# anpu.net
KiCad netlist of a schematic drawn in EAGLE
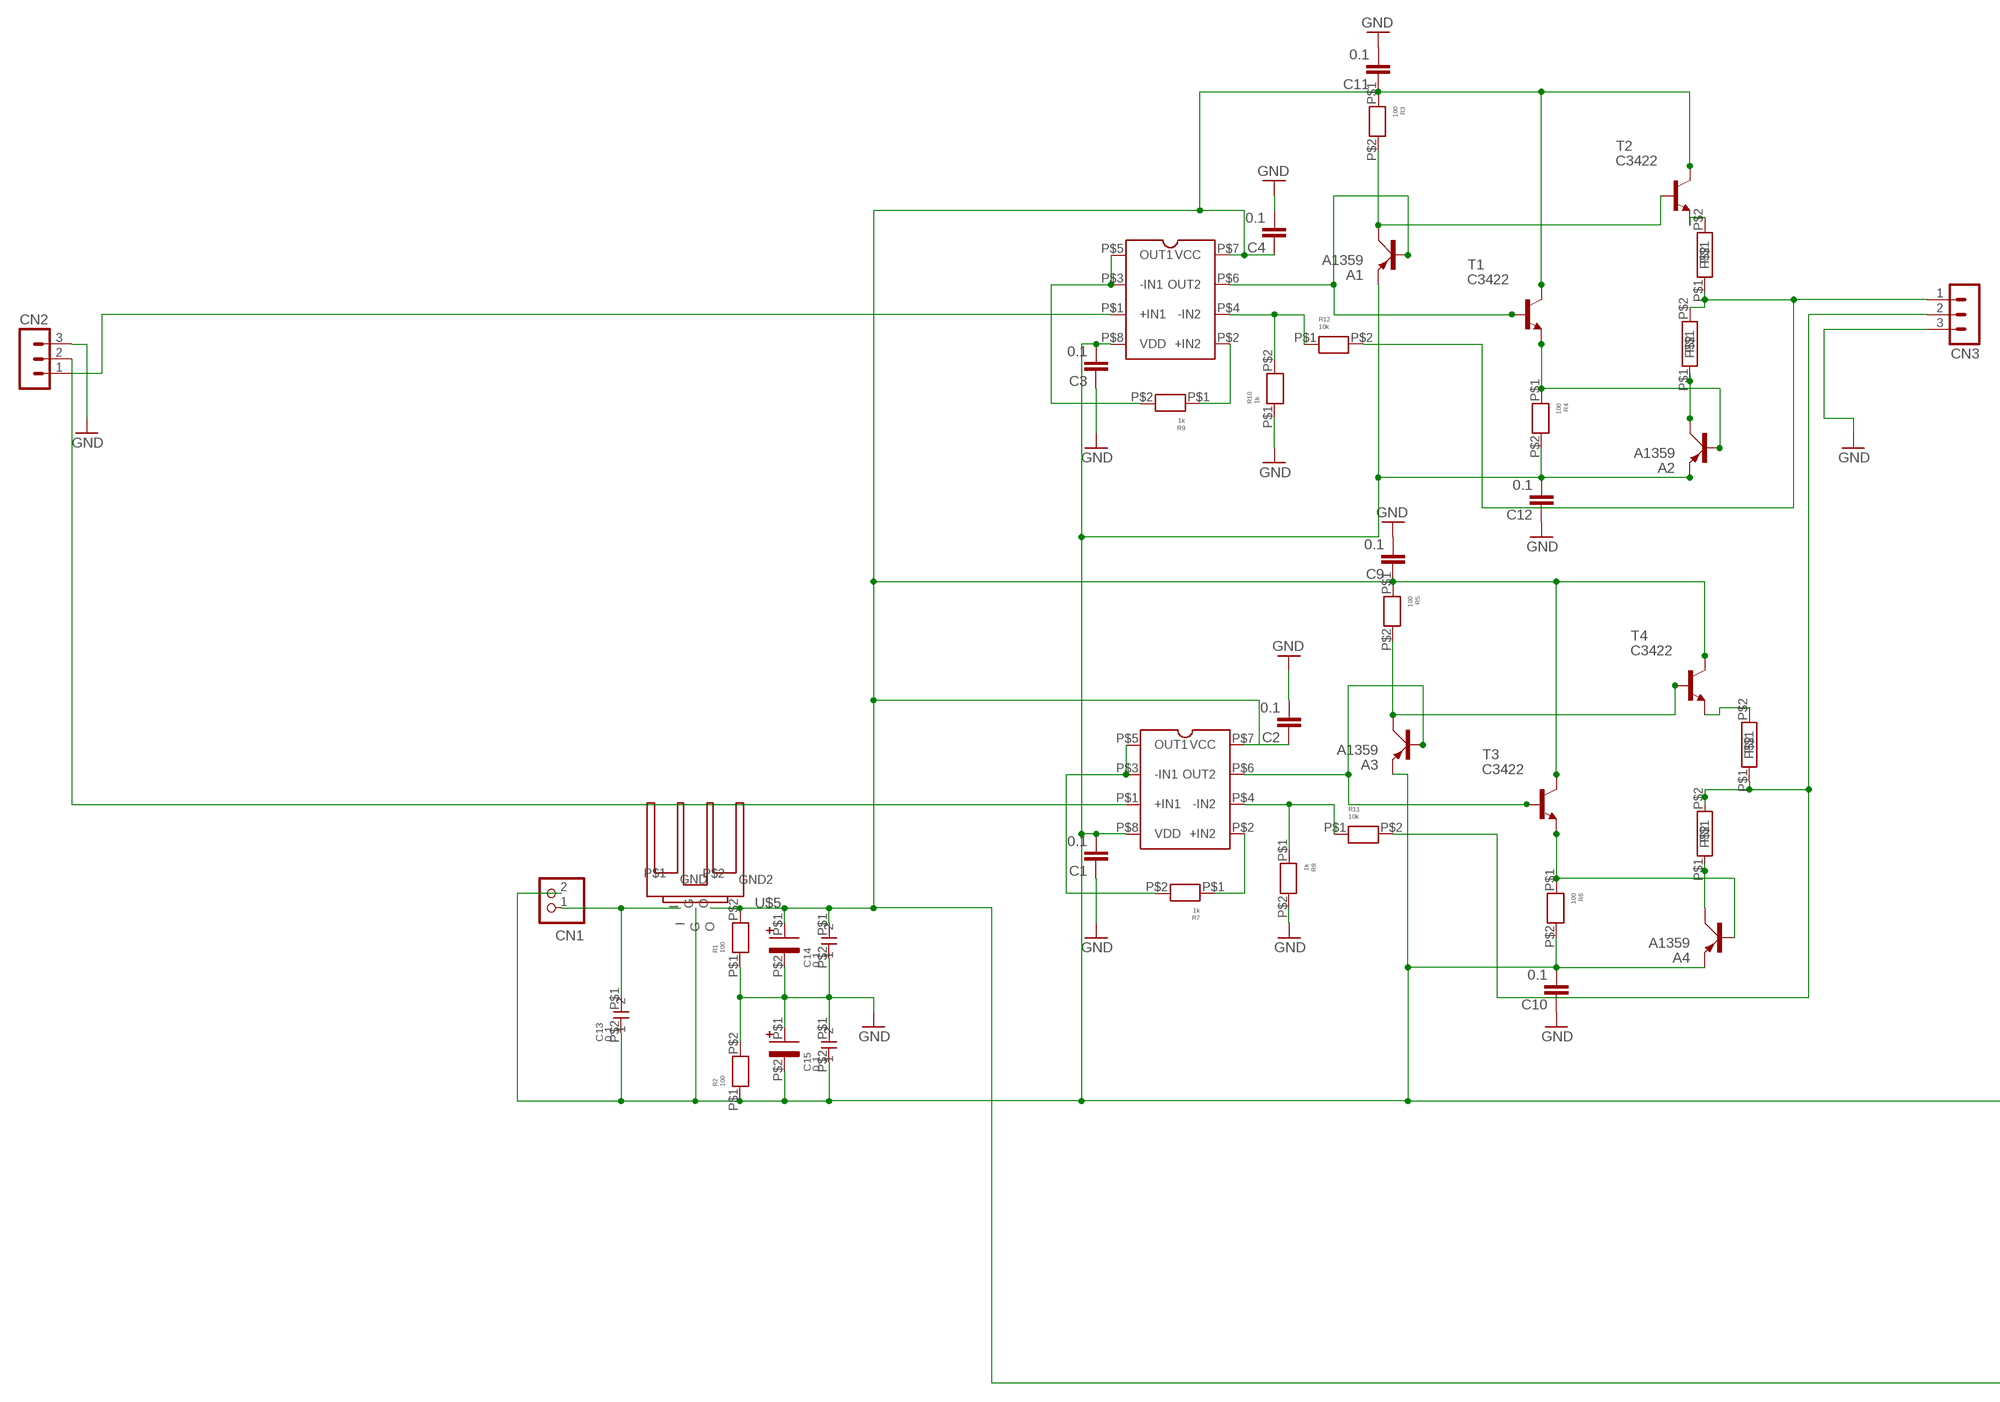
[diagram p0: schematic, sheet 1, part 1 of 2]
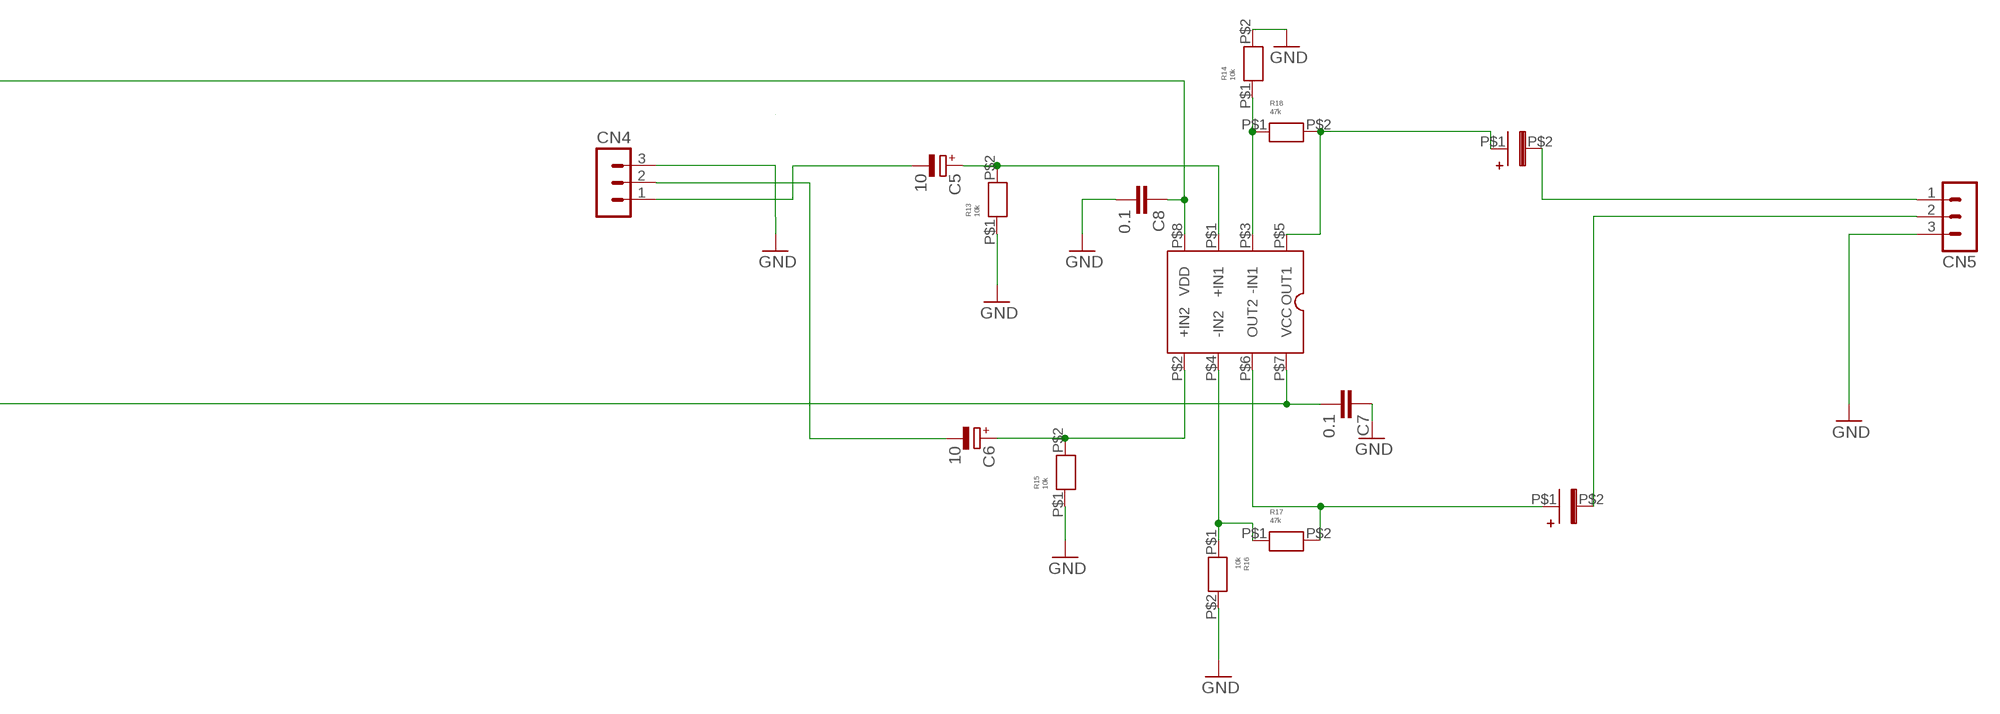
[diagram p1: schematic, sheet 1, part 2 of 2]

(export (version "E")
  (design (tool "Eeschema 10.0.6"))
  (components
    (comp (ref "A1")
      (value "A1359")
      (footprint "eagle-import:TO220AV")
      (libsource (lib "eagle-import") (part "MJE2955"))
    )
    (comp (ref "A2")
      (value "A1359")
      (footprint "eagle-import:TO220AV")
      (libsource (lib "eagle-import") (part "MJE2955"))
    )
    (comp (ref "A3")
      (value "A1359")
      (footprint "eagle-import:TO220AV")
      (libsource (lib "eagle-import") (part "MJE2955"))
    )
    (comp (ref "A4")
      (value "A1359")
      (footprint "eagle-import:TO220AV")
      (libsource (lib "eagle-import") (part "MJE2955"))
    )
    (comp (ref "C1")
      (value "0.1")
      (footprint "eagle-import:C050-030X075")
      (libsource (lib "eagle-import") (part "C-EU050-030X075"))
    )
    (comp (ref "C2")
      (value "0.1")
      (footprint "eagle-import:C050-030X075")
      (libsource (lib "eagle-import") (part "C-EU050-030X075"))
    )
    (comp (ref "C3")
      (value "0.1")
      (footprint "eagle-import:C050-030X075")
      (libsource (lib "eagle-import") (part "C-EU050-030X075"))
    )
    (comp (ref "C4")
      (value "0.1")
      (footprint "eagle-import:C050-030X075")
      (libsource (lib "eagle-import") (part "C-EU050-030X075"))
    )
    (comp (ref "C5")
      (value "10")
      (footprint "eagle-import:E2,5-5")
      (libsource (lib "eagle-import") (part "CPOL-EUE2.5-5"))
    )
    (comp (ref "C6")
      (value "10")
      (footprint "eagle-import:E2,5-5")
      (libsource (lib "eagle-import") (part "CPOL-EUE2.5-5"))
    )
    (comp (ref "C7")
      (value "0.1")
      (footprint "eagle-import:C050-030X075")
      (libsource (lib "eagle-import") (part "C-EU050-030X075"))
    )
    (comp (ref "C8")
      (value "0.1")
      (footprint "eagle-import:C050-030X075")
      (libsource (lib "eagle-import") (part "C-EU050-030X075"))
    )
    (comp (ref "C9")
      (value "0.1")
      (footprint "eagle-import:C050-030X075")
      (libsource (lib "eagle-import") (part "C-EU050-030X075"))
    )
    (comp (ref "C10")
      (value "0.1")
      (footprint "eagle-import:C050-030X075")
      (libsource (lib "eagle-import") (part "C-EU050-030X075"))
    )
    (comp (ref "C11")
      (value "0.1")
      (footprint "eagle-import:C050-030X075")
      (libsource (lib "eagle-import") (part "C-EU050-030X075"))
    )
    (comp (ref "C12")
      (value "0.1")
      (footprint "eagle-import:C050-030X075")
      (libsource (lib "eagle-import") (part "C-EU050-030X075"))
    )
    (comp (ref "C13")
      (value "0.1")
      (footprint "eagle-import:CON")
      (libsource (lib "eagle-import") (part "1608"))
    )
    (comp (ref "C14")
      (value "0.1")
      (footprint "eagle-import:CON")
      (libsource (lib "eagle-import") (part "1608"))
    )
    (comp (ref "C15")
      (value "0.1")
      (footprint "eagle-import:CON")
      (libsource (lib "eagle-import") (part "1608"))
    )
    (comp (ref "CN1")
      (value "B2B-XH-A")
      (footprint "eagle-import:B2B-XH-A")
      (libsource (lib "eagle-import") (part "B2B-XH-A"))
    )
    (comp (ref "CN2")
      (value "B3B-PH-K-S")
      (footprint "eagle-import:B3B-PH-K-S")
      (libsource (lib "eagle-import") (part "B3B-PH-K-S"))
    )
    (comp (ref "CN3")
      (value "B3B-PH-K-S")
      (footprint "eagle-import:B3B-PH-K-S")
      (libsource (lib "eagle-import") (part "B3B-PH-K-S"))
    )
    (comp (ref "CN4")
      (value "B3B-PH-K-S")
      (footprint "eagle-import:B3B-PH-K-S")
      (libsource (lib "eagle-import") (part "B3B-PH-K-S"))
    )
    (comp (ref "CN5")
      (value "B3B-PH-K-S")
      (footprint "eagle-import:B3B-PH-K-S")
      (libsource (lib "eagle-import") (part "B3B-PH-K-S"))
    )
    (comp (ref "EC1") (value "FG") (footprint "eagle-import:FG") (libsource (lib "eagle-import") (part "FG")))
    (comp (ref "EC2") (value "FG") (footprint "eagle-import:FG") (libsource (lib "eagle-import") (part "FG")))
    (comp (ref "EC3") (value "FG") (footprint "eagle-import:FG") (libsource (lib "eagle-import") (part "FG")))
    (comp (ref "EC4") (value "FG") (footprint "eagle-import:FG") (libsource (lib "eagle-import") (part "FG")))
    (comp (ref "R1")
      (value "100")
      (footprint "eagle-import:1608")
      (libsource (lib "eagle-import") (part "R"))
    )
    (comp (ref "R2")
      (value "100")
      (footprint "eagle-import:1608")
      (libsource (lib "eagle-import") (part "R"))
    )
    (comp (ref "R3")
      (value "100")
      (footprint "eagle-import:1608")
      (libsource (lib "eagle-import") (part "R"))
    )
    (comp (ref "R4")
      (value "100")
      (footprint "eagle-import:1608")
      (libsource (lib "eagle-import") (part "R"))
    )
    (comp (ref "R5")
      (value "100")
      (footprint "eagle-import:1608")
      (libsource (lib "eagle-import") (part "R"))
    )
    (comp (ref "R6")
      (value "100")
      (footprint "eagle-import:1608")
      (libsource (lib "eagle-import") (part "R"))
    )
    (comp (ref "R7") (value "1k") (footprint "eagle-import:1608") (libsource (lib "eagle-import") (part "R")))
    (comp (ref "R8") (value "1k") (footprint "eagle-import:1608") (libsource (lib "eagle-import") (part "R")))
    (comp (ref "R9") (value "1k") (footprint "eagle-import:1608") (libsource (lib "eagle-import") (part "R")))
    (comp (ref "R10")
      (value "1k")
      (footprint "eagle-import:1608")
      (libsource (lib "eagle-import") (part "R"))
    )
    (comp (ref "R11")
      (value "10k")
      (footprint "eagle-import:1608")
      (libsource (lib "eagle-import") (part "R"))
    )
    (comp (ref "R12")
      (value "10k")
      (footprint "eagle-import:1608")
      (libsource (lib "eagle-import") (part "R"))
    )
    (comp (ref "R13")
      (value "10k")
      (footprint "eagle-import:1608")
      (libsource (lib "eagle-import") (part "R"))
    )
    (comp (ref "R14")
      (value "10k")
      (footprint "eagle-import:1608")
      (libsource (lib "eagle-import") (part "R"))
    )
    (comp (ref "R15")
      (value "10k")
      (footprint "eagle-import:1608")
      (libsource (lib "eagle-import") (part "R"))
    )
    (comp (ref "R16")
      (value "10k")
      (footprint "eagle-import:1608")
      (libsource (lib "eagle-import") (part "R"))
    )
    (comp (ref "R17")
      (value "47k")
      (footprint "eagle-import:1608")
      (libsource (lib "eagle-import") (part "R"))
    )
    (comp (ref "R18")
      (value "47k")
      (footprint "eagle-import:1608")
      (libsource (lib "eagle-import") (part "R"))
    )
    (comp (ref "T1")
      (value "C3422")
      (footprint "eagle-import:TO220AV")
      (libsource (lib "eagle-import") (part "2SC3212V"))
    )
    (comp (ref "T2")
      (value "C3422")
      (footprint "eagle-import:TO220AV")
      (libsource (lib "eagle-import") (part "2SC3212V"))
    )
    (comp (ref "T3")
      (value "C3422")
      (footprint "eagle-import:TO220AV")
      (libsource (lib "eagle-import") (part "2SC3212V"))
    )
    (comp (ref "T4")
      (value "C3422")
      (footprint "eagle-import:TO220AV")
      (libsource (lib "eagle-import") (part "2SC3212V"))
    )
    (comp (ref "U$1")
      (value "4580DD")
      (footprint "eagle-import:4580DD")
      (libsource (lib "eagle-import") (part "4580DD"))
    )
    (comp (ref "U$4")
      (value "4580DD")
      (footprint "eagle-import:4580DD")
      (libsource (lib "eagle-import") (part "4580DD"))
    )
    (comp (ref "U$5")
      (value "CONVERTER")
      (footprint "eagle-import:CONVERTER")
      (libsource (lib "eagle-import") (part "CONVERTER"))
    )
    (comp (ref "U$6")
      (value "4580DD")
      (footprint "eagle-import:4580DD")
      (libsource (lib "eagle-import") (part "4580DD"))
    )
    (comp (ref "U$36")
      (value "0.47")
      (footprint "eagle-import:KINZOKUTEIKOU")
      (libsource (lib "eagle-import") (part "KINZOKUTEIKOU"))
    )
    (comp (ref "U$37")
      (value "0.47")
      (footprint "eagle-import:KINZOKUTEIKOU")
      (libsource (lib "eagle-import") (part "KINZOKUTEIKOU"))
    )
    (comp (ref "U$38")
      (value "0.47")
      (footprint "eagle-import:KINZOKUTEIKOU")
      (libsource (lib "eagle-import") (part "KINZOKUTEIKOU"))
    )
    (comp (ref "U$39")
      (value "0.47")
      (footprint "eagle-import:KINZOKUTEIKOU")
      (libsource (lib "eagle-import") (part "KINZOKUTEIKOU"))
    )
  )
  (nets
    (net (code "1") (name "GND") (class "Default")
      (node (ref "C1") (pin "1") (pinfunction "1_1") (pintype "passive"))
      (node (ref "C10") (pin "1") (pinfunction "1_1") (pintype "passive"))
      (node (ref "C11") (pin "2") (pinfunction "2_2") (pintype "passive"))
      (node (ref "C12") (pin "1") (pinfunction "1_1") (pintype "passive"))
      (node (ref "C14") (pin "P$2") (pinfunction "2_P$2") (pintype "bidirectional"))
      (node (ref "C15") (pin "P$1") (pinfunction "1_P$1") (pintype "bidirectional"))
      (node (ref "C2") (pin "2") (pinfunction "2_2") (pintype "passive"))
      (node (ref "C3") (pin "1") (pinfunction "1_1") (pintype "passive"))
      (node (ref "C4") (pin "2") (pinfunction "2_2") (pintype "passive"))
      (node (ref "C7") (pin "1") (pinfunction "1_1") (pintype "passive"))
      (node (ref "C8") (pin "2") (pinfunction "2_2") (pintype "passive"))
      (node (ref "C9") (pin "2") (pinfunction "2_2") (pintype "passive"))
      (node (ref "CN2") (pin "3") (pinfunction "3_3") (pintype "passive"))
      (node (ref "CN3") (pin "3") (pinfunction "3_3") (pintype "passive"))
      (node (ref "CN5") (pin "3") (pinfunction "3_3") (pintype "passive"))
      (node (ref "EC3") (pin "P$2") (pinfunction "P$1_P$2") (pintype "bidirectional"))
      (node (ref "EC4") (pin "P$1") (pinfunction "P$2_P$1") (pintype "bidirectional"))
      (node (ref "R1") (pin "P$1") (pinfunction "P$1_P$1") (pintype "bidirectional"))
      (node (ref "R10") (pin "P$1") (pinfunction "P$1_P$1") (pintype "bidirectional"))
      (node (ref "R13") (pin "P$1") (pinfunction "P$1_P$1") (pintype "bidirectional"))
      (node (ref "R14") (pin "P$2") (pinfunction "P$2_P$2") (pintype "bidirectional"))
      (node (ref "R15") (pin "P$1") (pinfunction "P$1_P$1") (pintype "bidirectional"))
      (node (ref "R16") (pin "P$2") (pinfunction "P$2_P$2") (pintype "bidirectional"))
      (node (ref "R2") (pin "P$2") (pinfunction "P$2_P$2") (pintype "bidirectional"))
      (node (ref "R8") (pin "P$2") (pinfunction "P$2_P$2") (pintype "bidirectional"))
    )
    (net (code "2") (name "Net-(A2-PadC)") (class "Default")
      (node (ref "A2") (pin "C") (pinfunction "C_C") (pintype "passive"))
      (node (ref "U$36") (pin "P$1") (pinfunction "P$1_P$1") (pintype "bidirectional"))
    )
    (net (code "3") (name "Net-(A4-PadC)") (class "Default")
      (node (ref "A4") (pin "C") (pinfunction "C_C") (pintype "passive"))
      (node (ref "U$39") (pin "P$1") (pinfunction "P$1_P$1") (pintype "bidirectional"))
    )
    (net (code "4") (name "Net-(C5-Pad-)") (class "Default")
      (node (ref "C5") (pin "-") (pinfunction "-_-") (pintype "passive"))
      (node (ref "CN4") (pin "1") (pinfunction "1_1") (pintype "passive"))
    )
    (net (code "5") (name "Net-(C6-Pad-)") (class "Default")
      (node (ref "C6") (pin "-") (pinfunction "-_-") (pintype "passive"))
      (node (ref "CN4") (pin "2") (pinfunction "2_2") (pintype "passive"))
    )
    (net (code "6") (name "Net-(C13-1)") (class "Default")
      (node (ref "C13") (pin "P$1") (pinfunction "1_P$1") (pintype "bidirectional"))
      (node (ref "CN1") (pin "1") (pinfunction "1_1") (pintype "passive"))
      (node (ref "U$5") (pin "I") (pinfunction "I_I") (pintype "bidirectional"))
    )
    (net (code "7") (name "Net-(C13-2)") (class "Default")
      (node (ref "A1") (pin "E") (pinfunction "E_E") (pintype "passive"))
      (node (ref "A2") (pin "E") (pinfunction "E_E") (pintype "passive"))
      (node (ref "A3") (pin "E") (pinfunction "E_E") (pintype "passive"))
      (node (ref "A4") (pin "E") (pinfunction "E_E") (pintype "passive"))
      (node (ref "C1") (pin "2") (pinfunction "2_2") (pintype "passive"))
      (node (ref "C10") (pin "2") (pinfunction "2_2") (pintype "passive"))
      (node (ref "C12") (pin "2") (pinfunction "2_2") (pintype "passive"))
      (node (ref "C13") (pin "P$2") (pinfunction "2_P$2") (pintype "bidirectional"))
      (node (ref "C15") (pin "P$2") (pinfunction "2_P$2") (pintype "bidirectional"))
      (node (ref "C3") (pin "2") (pinfunction "2_2") (pintype "passive"))
      (node (ref "C8") (pin "1") (pinfunction "1_1") (pintype "passive"))
      (node (ref "CN1") (pin "2") (pinfunction "2_2") (pintype "passive"))
      (node (ref "EC4") (pin "P$2") (pinfunction "P$1_P$2") (pintype "bidirectional"))
      (node (ref "R2") (pin "P$1") (pinfunction "P$1_P$1") (pintype "bidirectional"))
      (node (ref "R4") (pin "P$2") (pinfunction "P$2_P$2") (pintype "bidirectional"))
      (node (ref "R6") (pin "P$2") (pinfunction "P$2_P$2") (pintype "bidirectional"))
      (node (ref "U$1") (pin "P$8") (pinfunction "VDD_P$8") (pintype "bidirectional"))
      (node (ref "U$4") (pin "P$8") (pinfunction "VDD_P$8") (pintype "bidirectional"))
      (node (ref "U$5") (pin "G") (pinfunction "G_G") (pintype "bidirectional"))
      (node (ref "U$6") (pin "P$8") (pinfunction "VDD_P$8") (pintype "bidirectional"))
    )
    (net (code "8") (name "Net-(C14-1)") (class "Default")
      (node (ref "C11") (pin "1") (pinfunction "1_1") (pintype "passive"))
      (node (ref "C14") (pin "P$1") (pinfunction "1_P$1") (pintype "bidirectional"))
      (node (ref "C2") (pin "1") (pinfunction "1_1") (pintype "passive"))
      (node (ref "C4") (pin "1") (pinfunction "1_1") (pintype "passive"))
      (node (ref "C7") (pin "2") (pinfunction "2_2") (pintype "passive"))
      (node (ref "C9") (pin "1") (pinfunction "1_1") (pintype "passive"))
      (node (ref "EC3") (pin "P$1") (pinfunction "P$2_P$1") (pintype "bidirectional"))
      (node (ref "R1") (pin "P$2") (pinfunction "P$2_P$2") (pintype "bidirectional"))
      (node (ref "R3") (pin "P$1") (pinfunction "P$1_P$1") (pintype "bidirectional"))
      (node (ref "R5") (pin "P$1") (pinfunction "P$1_P$1") (pintype "bidirectional"))
      (node (ref "T1") (pin "2") (pinfunction "C_2") (pintype "passive"))
      (node (ref "T2") (pin "2") (pinfunction "C_2") (pintype "passive"))
      (node (ref "T3") (pin "2") (pinfunction "C_2") (pintype "passive"))
      (node (ref "T4") (pin "2") (pinfunction "C_2") (pintype "passive"))
      (node (ref "U$1") (pin "P$7") (pinfunction "VCC_P$7") (pintype "bidirectional"))
      (node (ref "U$4") (pin "P$7") (pinfunction "VCC_P$7") (pintype "bidirectional"))
      (node (ref "U$5") (pin "O") (pinfunction "O_O") (pintype "bidirectional"))
      (node (ref "U$6") (pin "P$7") (pinfunction "VCC_P$7") (pintype "bidirectional"))
    )
    (net (code "9") (name "Net-(CN3-Pad1)") (class "Default")
      (node (ref "CN3") (pin "1") (pinfunction "1_1") (pintype "passive"))
      (node (ref "R12") (pin "P$2") (pinfunction "P$2_P$2") (pintype "bidirectional"))
      (node (ref "U$36") (pin "P$2") (pinfunction "P$2_P$2") (pintype "bidirectional"))
      (node (ref "U$37") (pin "P$1") (pinfunction "P$1_P$1") (pintype "bidirectional"))
    )
    (net (code "10") (name "Net-(CN3-Pad2)") (class "Default")
      (node (ref "CN3") (pin "2") (pinfunction "2_2") (pintype "passive"))
      (node (ref "R11") (pin "P$2") (pinfunction "P$2_P$2") (pintype "bidirectional"))
      (node (ref "U$38") (pin "P$1") (pinfunction "P$1_P$1") (pintype "bidirectional"))
      (node (ref "U$39") (pin "P$2") (pinfunction "P$2_P$2") (pintype "bidirectional"))
    )
    (net (code "11") (name "Net-(EC1-P$1)") (class "Default")
      (node (ref "CN5") (pin "2") (pinfunction "2_2") (pintype "passive"))
      (node (ref "EC1") (pin "P$2") (pinfunction "P$1_P$2") (pintype "bidirectional"))
    )
    (net (code "12") (name "Net-(EC1-P$2)") (class "Default")
      (node (ref "EC1") (pin "P$1") (pinfunction "P$2_P$1") (pintype "bidirectional"))
      (node (ref "R17") (pin "P$2") (pinfunction "P$2_P$2") (pintype "bidirectional"))
      (node (ref "U$6") (pin "P$6") (pinfunction "OUT2_P$6") (pintype "bidirectional"))
    )
    (net (code "13") (name "Net-(EC2-P$1)") (class "Default")
      (node (ref "CN5") (pin "1") (pinfunction "1_1") (pintype "passive"))
      (node (ref "EC2") (pin "P$2") (pinfunction "P$1_P$2") (pintype "bidirectional"))
    )
    (net (code "14") (name "Net-(EC2-P$2)") (class "Default")
      (node (ref "EC2") (pin "P$1") (pinfunction "P$2_P$1") (pintype "bidirectional"))
      (node (ref "R18") (pin "P$2") (pinfunction "P$2_P$2") (pintype "bidirectional"))
      (node (ref "U$6") (pin "P$5") (pinfunction "OUT1_P$5") (pintype "bidirectional"))
    )
    (net (code "15") (name "Net-(T1-B)") (class "Default")
      (node (ref "A1") (pin "B") (pinfunction "B_B") (pintype "passive"))
      (node (ref "T1") (pin "1") (pinfunction "B_1") (pintype "passive"))
      (node (ref "U$4") (pin "P$6") (pinfunction "OUT2_P$6") (pintype "bidirectional"))
    )
    (net (code "16") (name "Net-(T1-E)") (class "Default")
      (node (ref "A2") (pin "B") (pinfunction "B_B") (pintype "passive"))
      (node (ref "R4") (pin "P$1") (pinfunction "P$1_P$1") (pintype "bidirectional"))
      (node (ref "T1") (pin "3") (pinfunction "E_3") (pintype "passive"))
    )
    (net (code "17") (name "Net-(T2-B)") (class "Default")
      (node (ref "A1") (pin "C") (pinfunction "C_C") (pintype "passive"))
      (node (ref "R3") (pin "P$2") (pinfunction "P$2_P$2") (pintype "bidirectional"))
      (node (ref "T2") (pin "1") (pinfunction "B_1") (pintype "passive"))
    )
    (net (code "18") (name "Net-(T2-E)") (class "Default")
      (node (ref "T2") (pin "3") (pinfunction "E_3") (pintype "passive"))
      (node (ref "U$37") (pin "P$2") (pinfunction "P$2_P$2") (pintype "bidirectional"))
    )
    (net (code "19") (name "Net-(T3-B)") (class "Default")
      (node (ref "A3") (pin "B") (pinfunction "B_B") (pintype "passive"))
      (node (ref "T3") (pin "1") (pinfunction "B_1") (pintype "passive"))
      (node (ref "U$1") (pin "P$6") (pinfunction "OUT2_P$6") (pintype "bidirectional"))
    )
    (net (code "20") (name "Net-(T3-E)") (class "Default")
      (node (ref "A4") (pin "B") (pinfunction "B_B") (pintype "passive"))
      (node (ref "R6") (pin "P$1") (pinfunction "P$1_P$1") (pintype "bidirectional"))
      (node (ref "T3") (pin "3") (pinfunction "E_3") (pintype "passive"))
    )
    (net (code "21") (name "Net-(T4-B)") (class "Default")
      (node (ref "A3") (pin "C") (pinfunction "C_C") (pintype "passive"))
      (node (ref "R5") (pin "P$2") (pinfunction "P$2_P$2") (pintype "bidirectional"))
      (node (ref "T4") (pin "1") (pinfunction "B_1") (pintype "passive"))
    )
    (net (code "22") (name "Net-(T4-E)") (class "Default")
      (node (ref "T4") (pin "3") (pinfunction "E_3") (pintype "passive"))
      (node (ref "U$38") (pin "P$2") (pinfunction "P$2_P$2") (pintype "bidirectional"))
    )
    (net (code "23") (name "Net-(U$1-+IN1)") (class "Default")
      (node (ref "CN2") (pin "2") (pinfunction "2_2") (pintype "passive"))
      (node (ref "U$1") (pin "P$1") (pinfunction "+IN1_P$1") (pintype "bidirectional"))
    )
    (net (code "24") (name "Net-(U$1-+IN2)") (class "Default")
      (node (ref "R7") (pin "P$1") (pinfunction "P$1_P$1") (pintype "bidirectional"))
      (node (ref "U$1") (pin "P$2") (pinfunction "+IN2_P$2") (pintype "bidirectional"))
    )
    (net (code "25") (name "Net-(U$1--IN1)") (class "Default")
      (node (ref "R7") (pin "P$2") (pinfunction "P$2_P$2") (pintype "bidirectional"))
      (node (ref "U$1") (pin "P$3") (pinfunction "-IN1_P$3") (pintype "bidirectional"))
      (node (ref "U$1") (pin "P$5") (pinfunction "OUT1_P$5") (pintype "bidirectional"))
    )
    (net (code "26") (name "Net-(U$1--IN2)") (class "Default")
      (node (ref "R11") (pin "P$1") (pinfunction "P$1_P$1") (pintype "bidirectional"))
      (node (ref "R8") (pin "P$1") (pinfunction "P$1_P$1") (pintype "bidirectional"))
      (node (ref "U$1") (pin "P$4") (pinfunction "-IN2_P$4") (pintype "bidirectional"))
    )
    (net (code "27") (name "Net-(U$4-+IN1)") (class "Default")
      (node (ref "CN2") (pin "1") (pinfunction "1_1") (pintype "passive"))
      (node (ref "U$4") (pin "P$1") (pinfunction "+IN1_P$1") (pintype "bidirectional"))
    )
    (net (code "28") (name "Net-(U$4-+IN2)") (class "Default")
      (node (ref "R9") (pin "P$1") (pinfunction "P$1_P$1") (pintype "bidirectional"))
      (node (ref "U$4") (pin "P$2") (pinfunction "+IN2_P$2") (pintype "bidirectional"))
    )
    (net (code "29") (name "Net-(U$4--IN1)") (class "Default")
      (node (ref "R9") (pin "P$2") (pinfunction "P$2_P$2") (pintype "bidirectional"))
      (node (ref "U$4") (pin "P$3") (pinfunction "-IN1_P$3") (pintype "bidirectional"))
      (node (ref "U$4") (pin "P$5") (pinfunction "OUT1_P$5") (pintype "bidirectional"))
    )
    (net (code "30") (name "Net-(U$4--IN2)") (class "Default")
      (node (ref "R10") (pin "P$2") (pinfunction "P$2_P$2") (pintype "bidirectional"))
      (node (ref "R12") (pin "P$1") (pinfunction "P$1_P$1") (pintype "bidirectional"))
      (node (ref "U$4") (pin "P$4") (pinfunction "-IN2_P$4") (pintype "bidirectional"))
    )
    (net (code "31") (name "Net-(U$6-+IN1)") (class "Default")
      (node (ref "C5") (pin "+") (pinfunction "+_+") (pintype "passive"))
      (node (ref "R13") (pin "P$2") (pinfunction "P$2_P$2") (pintype "bidirectional"))
      (node (ref "U$6") (pin "P$1") (pinfunction "+IN1_P$1") (pintype "bidirectional"))
    )
    (net (code "32") (name "Net-(U$6-+IN2)") (class "Default")
      (node (ref "C6") (pin "+") (pinfunction "+_+") (pintype "passive"))
      (node (ref "R15") (pin "P$2") (pinfunction "P$2_P$2") (pintype "bidirectional"))
      (node (ref "U$6") (pin "P$2") (pinfunction "+IN2_P$2") (pintype "bidirectional"))
    )
    (net (code "33") (name "Net-(U$6--IN1)") (class "Default")
      (node (ref "R14") (pin "P$1") (pinfunction "P$1_P$1") (pintype "bidirectional"))
      (node (ref "R18") (pin "P$1") (pinfunction "P$1_P$1") (pintype "bidirectional"))
      (node (ref "U$6") (pin "P$3") (pinfunction "-IN1_P$3") (pintype "bidirectional"))
    )
    (net (code "34") (name "Net-(U$6--IN2)") (class "Default")
      (node (ref "R16") (pin "P$1") (pinfunction "P$1_P$1") (pintype "bidirectional"))
      (node (ref "R17") (pin "P$1") (pinfunction "P$1_P$1") (pintype "bidirectional"))
      (node (ref "U$6") (pin "P$4") (pinfunction "-IN2_P$4") (pintype "bidirectional"))
    )
    (net (code "35") (name "unconnected-(CN4-Pad3)") (class "Default")
      (node (ref "CN4") (pin "3") (pinfunction "3_3") (pintype "passive"))
    )
    (net (code "36") (name "unconnected-(U$5-GND-PadP$1)") (class "Default")
      (node (ref "U$5") (pin "P$1") (pinfunction "GND_P$1") (pintype "bidirectional"))
    )
    (net (code "37") (name "unconnected-(U$5-GND2-PadP$2)") (class "Default")
      (node (ref "U$5") (pin "P$2") (pinfunction "GND2_P$2") (pintype "bidirectional"))
    )
  )
)
